# driver.net
KiCad netlist of a schematic drawn in EAGLE
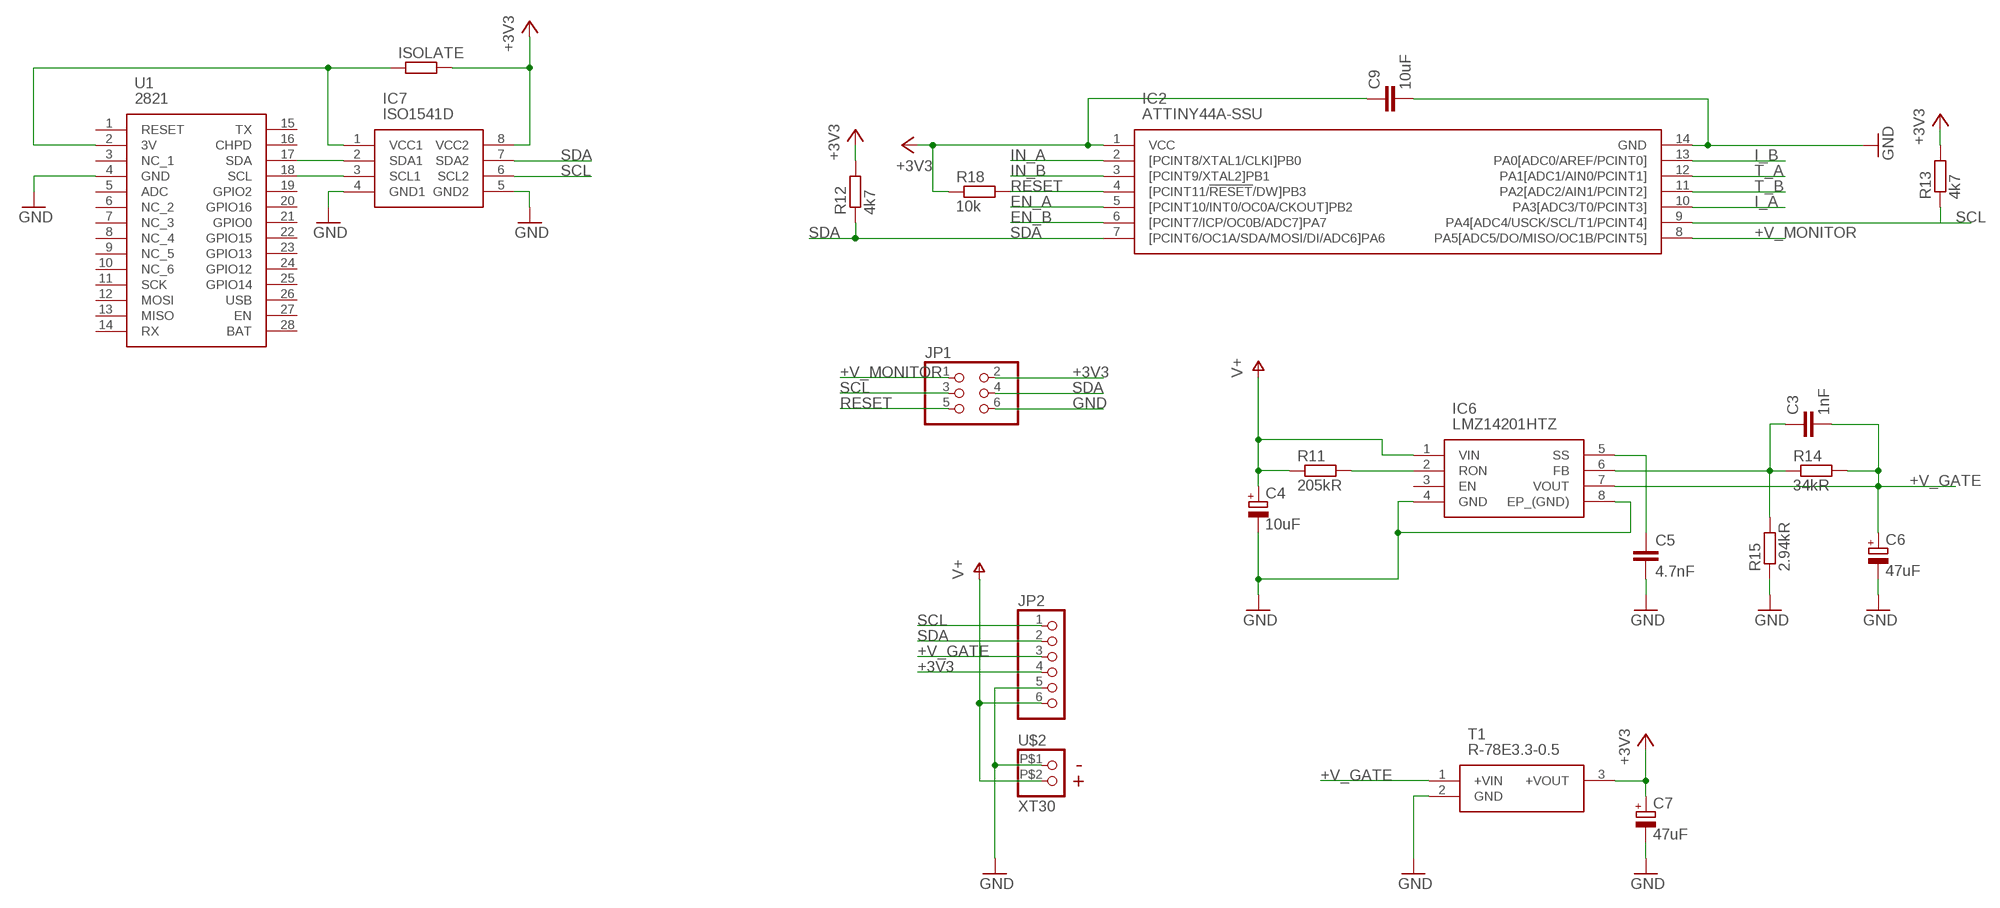
[diagram p0: schematic, sheet 1, part 1 of 2]
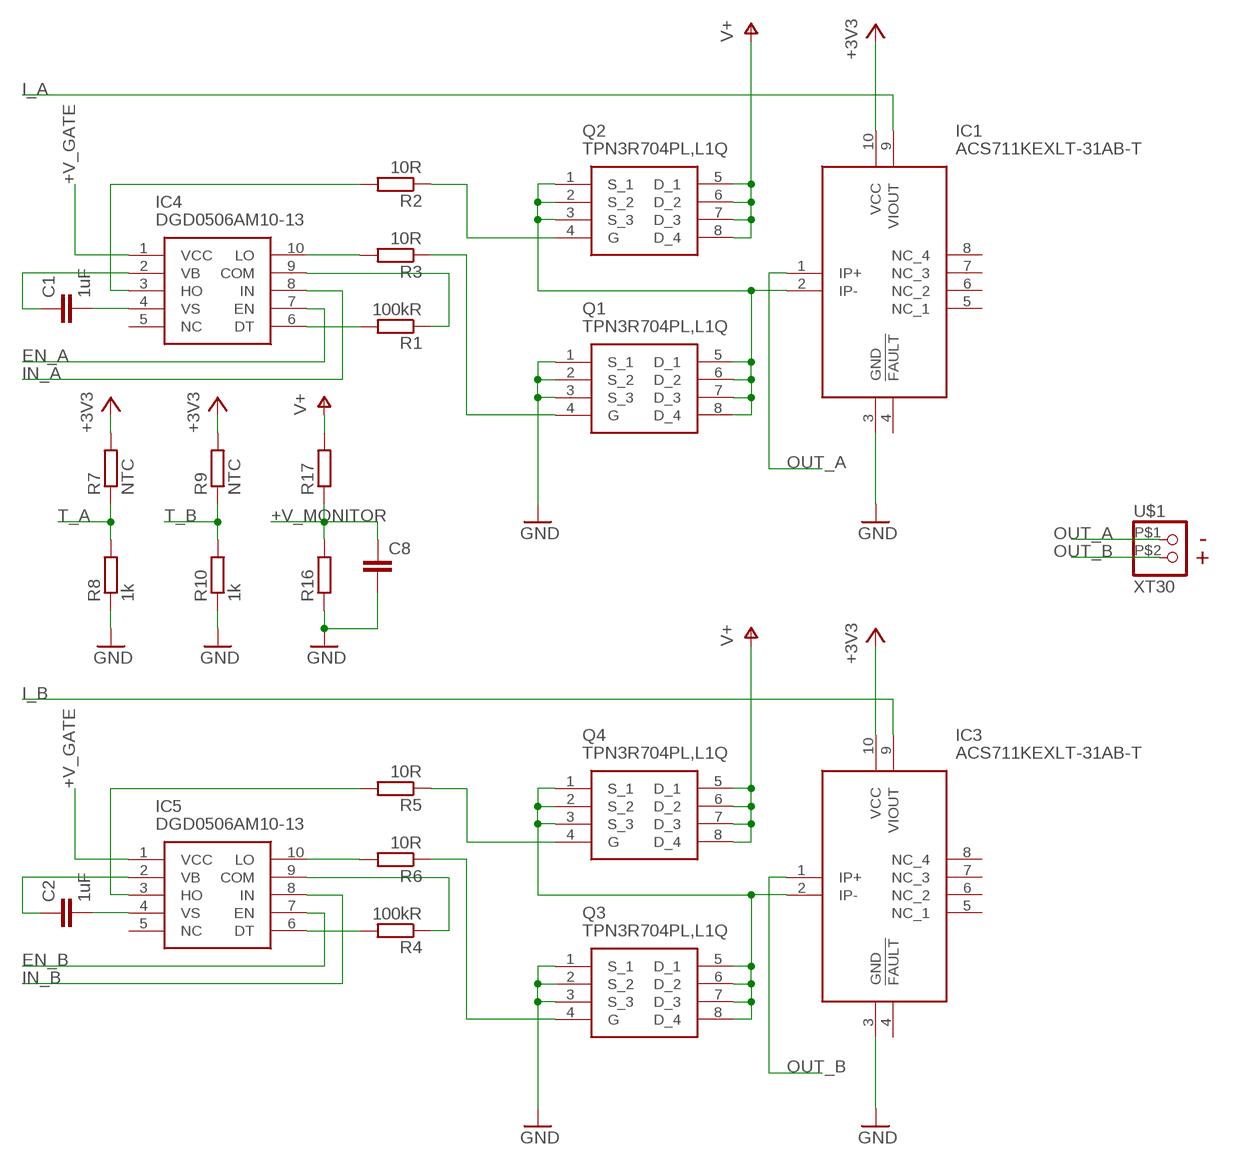
[diagram p1: schematic, sheet 1, part 2 of 2]

(export (version "E")
  (design (tool "Eeschema 10.0.6"))
  (components
    (comp (ref "C1")
      (value "1uF")
      (footprint "eagle-import:C0603")
      (libsource (lib "eagle-import") (part "C-EUC0603"))
    )
    (comp (ref "C2")
      (value "1uF")
      (footprint "eagle-import:C0603")
      (libsource (lib "eagle-import") (part "C-EUC0603"))
    )
    (comp (ref "C3")
      (value "1nF")
      (footprint "eagle-import:C0603")
      (libsource (lib "eagle-import") (part "C-EUC0603"))
    )
    (comp (ref "C4")
      (value "10uF")
      (footprint "eagle-import:E2,5-6E")
      (libsource (lib "eagle-import") (part "CPOL-EUE2,5-6E"))
    )
    (comp (ref "C5")
      (value "4.7nF")
      (footprint "eagle-import:C0603")
      (libsource (lib "eagle-import") (part "C-EUC0603"))
    )
    (comp (ref "C6")
      (value "47uF")
      (footprint "eagle-import:E2,5-6E")
      (libsource (lib "eagle-import") (part "CPOL-EUE2,5-6E"))
    )
    (comp (ref "C7")
      (value "47uF")
      (footprint "eagle-import:E2,5-6E")
      (libsource (lib "eagle-import") (part "CPOL-EUE2,5-6E"))
    )
    (comp (ref "C8")
      (value "C-EUC0603")
      (footprint "eagle-import:C0603")
      (libsource (lib "eagle-import") (part "C-EUC0603"))
    )
    (comp (ref "C9")
      (value "10uF")
      (footprint "eagle-import:C0603")
      (libsource (lib "eagle-import") (part "C-EUC0603"))
    )
    (comp (ref "IC1")
      (value "ACS711KEXLT-31AB-T")
      (footprint "eagle-import:EX-PACKAGE")
      (libsource (lib "eagle-import") (part "ACS711KEXLT-31AB-T"))
    )
    (comp (ref "IC2")
      (value "ATTINY44A-SSU")
      (footprint "eagle-import:SOIC127P600X175-14N")
      (fields
        (field (name "MOUSER_PART_NUMBER") "556-ATTINY44A-SSU")
        (field (name "RS_PART_NUMBER") "1331640P")
      )
      (libsource (lib "eagle-import") (part "ATTINY44A-SSU"))
    )
    (comp (ref "IC3")
      (value "ACS711KEXLT-31AB-T")
      (footprint "eagle-import:EX-PACKAGE")
      (libsource (lib "eagle-import") (part "ACS711KEXLT-31AB-T"))
    )
    (comp (ref "IC4")
      (value "DGD0506AM10-13")
      (footprint "eagle-import:SOP50P490X110-10N")
      (fields
        (field (name "MOUSER_PART_NUMBER") "621-DGD0506AM10-13")
        (field (name "RS_PART_NUMBER") "1827336P")
      )
      (libsource (lib "eagle-import") (part "DGD0506AM10-13"))
    )
    (comp (ref "IC5")
      (value "DGD0506AM10-13")
      (footprint "eagle-import:SOP50P490X110-10N")
      (fields
        (field (name "MOUSER_PART_NUMBER") "621-DGD0506AM10-13")
        (field (name "RS_PART_NUMBER") "1827336P")
      )
      (libsource (lib "eagle-import") (part "DGD0506AM10-13"))
    )
    (comp (ref "IC6")
      (value "LMZ14201HTZ")
      (footprint "eagle-import:NDW0007A")
      (libsource (lib "eagle-import") (part "LMZ14201HTZ"))
    )
    (comp (ref "IC7")
      (value "ISO1541D")
      (footprint "eagle-import:SOIC127P600X175-8N")
      (fields (field (name "MOUSER_PART_NUMBER") "595-ISO1541D") (field (name "RS_PART_NUMBER") "8253075P"))
      (libsource (lib "eagle-import") (part "ISO1541D"))
    )
    (comp (ref "ISOLATE")
      (value "R-EU_R0805")
      (footprint "eagle-import:R0805")
      (libsource (lib "eagle-import") (part "R-EU_R0805"))
    )
    (comp (ref "JP1")
      (value "PINHD-2X3")
      (footprint "eagle-import:2X03")
      (libsource (lib "eagle-import") (part "PINHD-2X3"))
    )
    (comp (ref "JP2")
      (value "PINHD-1X6")
      (footprint "eagle-import:1X06")
      (libsource (lib "eagle-import") (part "PINHD-1X6"))
    )
    (comp (ref "Q1")
      (value "TPN3R704PL,L1Q")
      (footprint "eagle-import:TSON_ADVANCE")
      (fields (field (name "MOUSER_PART_NUMBER") "757-TPN3R704PLL1Q"))
      (libsource (lib "eagle-import") (part "TPN3R704PL,L1Q"))
    )
    (comp (ref "Q2")
      (value "TPN3R704PL,L1Q")
      (footprint "eagle-import:TSON_ADVANCE")
      (fields (field (name "MOUSER_PART_NUMBER") "757-TPN3R704PLL1Q"))
      (libsource (lib "eagle-import") (part "TPN3R704PL,L1Q"))
    )
    (comp (ref "Q3")
      (value "TPN3R704PL,L1Q")
      (footprint "eagle-import:TSON_ADVANCE")
      (fields (field (name "MOUSER_PART_NUMBER") "757-TPN3R704PLL1Q"))
      (libsource (lib "eagle-import") (part "TPN3R704PL,L1Q"))
    )
    (comp (ref "Q4")
      (value "TPN3R704PL,L1Q")
      (footprint "eagle-import:TSON_ADVANCE")
      (fields (field (name "MOUSER_PART_NUMBER") "757-TPN3R704PLL1Q"))
      (libsource (lib "eagle-import") (part "TPN3R704PL,L1Q"))
    )
    (comp (ref "R1")
      (value "100kR")
      (footprint "eagle-import:R0603")
      (libsource (lib "eagle-import") (part "R-EU_R0603"))
    )
    (comp (ref "R2")
      (value "10R")
      (footprint "eagle-import:R0603")
      (libsource (lib "eagle-import") (part "R-EU_R0603"))
    )
    (comp (ref "R3")
      (value "10R")
      (footprint "eagle-import:R0603")
      (libsource (lib "eagle-import") (part "R-EU_R0603"))
    )
    (comp (ref "R4")
      (value "100kR")
      (footprint "eagle-import:R0603")
      (libsource (lib "eagle-import") (part "R-EU_R0603"))
    )
    (comp (ref "R5")
      (value "10R")
      (footprint "eagle-import:R0603")
      (libsource (lib "eagle-import") (part "R-EU_R0603"))
    )
    (comp (ref "R6")
      (value "10R")
      (footprint "eagle-import:R0603")
      (libsource (lib "eagle-import") (part "R-EU_R0603"))
    )
    (comp (ref "R7")
      (value "NTC")
      (footprint "eagle-import:R0603")
      (libsource (lib "eagle-import") (part "R-EU_R0603"))
    )
    (comp (ref "R8")
      (value "1k")
      (footprint "eagle-import:R0603")
      (libsource (lib "eagle-import") (part "R-EU_R0603"))
    )
    (comp (ref "R9")
      (value "NTC")
      (footprint "eagle-import:R0603")
      (libsource (lib "eagle-import") (part "R-EU_R0603"))
    )
    (comp (ref "R10")
      (value "1k")
      (footprint "eagle-import:R0603")
      (libsource (lib "eagle-import") (part "R-EU_R0603"))
    )
    (comp (ref "R11")
      (value "205kR")
      (footprint "eagle-import:R0603")
      (libsource (lib "eagle-import") (part "R-EU_R0603"))
    )
    (comp (ref "R12")
      (value "4k7")
      (footprint "eagle-import:R0603")
      (libsource (lib "eagle-import") (part "R-EU_R0603"))
    )
    (comp (ref "R13")
      (value "4k7")
      (footprint "eagle-import:R0603")
      (libsource (lib "eagle-import") (part "R-EU_R0603"))
    )
    (comp (ref "R14")
      (value "34kR")
      (footprint "eagle-import:R0603")
      (libsource (lib "eagle-import") (part "R-EU_R0603"))
    )
    (comp (ref "R15")
      (value "2.94kR")
      (footprint "eagle-import:R0603")
      (libsource (lib "eagle-import") (part "R-EU_R0603"))
    )
    (comp (ref "R16")
      (value "R-EU_R0603")
      (footprint "eagle-import:R0603")
      (libsource (lib "eagle-import") (part "R-EU_R0603"))
    )
    (comp (ref "R17")
      (value "R-EU_R0603")
      (footprint "eagle-import:R0603")
      (libsource (lib "eagle-import") (part "R-EU_R0603"))
    )
    (comp (ref "R18")
      (value "10k")
      (footprint "eagle-import:R0603")
      (libsource (lib "eagle-import") (part "R-EU_R0603"))
    )
    (comp (ref "T1")
      (value "R-78E3.3-0.5")
      (footprint "eagle-import:SHDRV3W100P0_254_1X3_1160X850X")
      (fields
        (field (name "MOUSER_PART_NUMBER") "919-R-78E3.3-0.5")
        (field (name "RS_PART_NUMBER") "1666497")
      )
      (libsource (lib "eagle-import") (part "R-78E3.3-0.5"))
    )
    (comp (ref "U$1")
      (value "XT30")
      (footprint "eagle-import:XT30")
      (libsource (lib "eagle-import") (part "XT30"))
    )
    (comp (ref "U$2")
      (value "XT30")
      (footprint "eagle-import:XT30")
      (libsource (lib "eagle-import") (part "XT30"))
    )
    (comp (ref "U1")
      (value "2821")
      (footprint "eagle-import:2821")
      (fields (field (name "MOUSER_PART_NUMBER") "485-2821") (field (name "RS_PART_NUMBER") "1245505"))
      (libsource (lib "eagle-import") (part "2821"))
    )
  )
  (nets
    (net (code "1") (name "+3V3") (class "Default")
      (node (ref "C7") (pin "+") (pinfunction "+_+") (pintype "passive"))
      (node (ref "C9") (pin "1") (pinfunction "1_1") (pintype "passive"))
      (node (ref "IC1") (pin "10") (pinfunction "VCC_10") (pintype "bidirectional"))
      (node (ref "IC2") (pin "1") (pinfunction "VCC_1") (pintype "power_in"))
      (node (ref "IC3") (pin "10") (pinfunction "VCC_10") (pintype "bidirectional"))
      (node (ref "IC7") (pin "8") (pinfunction "VCC2_8") (pintype "bidirectional"))
      (node (ref "ISOLATE") (pin "2") (pinfunction "2_2") (pintype "passive"))
      (node (ref "JP1") (pin "2") (pinfunction "2_2") (pintype "passive"))
      (node (ref "JP2") (pin "4") (pinfunction "4_4") (pintype "passive"))
      (node (ref "R12") (pin "2") (pinfunction "2_2") (pintype "passive"))
      (node (ref "R13") (pin "2") (pinfunction "2_2") (pintype "passive"))
      (node (ref "R18") (pin "1") (pinfunction "1_1") (pintype "passive"))
      (node (ref "R7") (pin "2") (pinfunction "2_2") (pintype "passive"))
      (node (ref "R9") (pin "2") (pinfunction "2_2") (pintype "passive"))
      (node (ref "T1") (pin "3") (pinfunction "+VOUT_3") (pintype "output"))
    )
    (net (code "2") (name "/+V_GATE") (class "Default")
      (node (ref "C3") (pin "2") (pinfunction "2_2") (pintype "passive"))
      (node (ref "C6") (pin "+") (pinfunction "+_+") (pintype "passive"))
      (node (ref "IC4") (pin "1") (pinfunction "VCC_1") (pintype "bidirectional"))
      (node (ref "IC5") (pin "1") (pinfunction "VCC_1") (pintype "bidirectional"))
      (node (ref "IC6") (pin "7") (pinfunction "VOUT_7") (pintype "bidirectional"))
      (node (ref "JP2") (pin "3") (pinfunction "3_3") (pintype "passive"))
      (node (ref "R14") (pin "2") (pinfunction "2_2") (pintype "passive"))
      (node (ref "T1") (pin "1") (pinfunction "+VIN_1") (pintype "input"))
    )
    (net (code "3") (name "/+V_MONITOR") (class "Default")
      (node (ref "C8") (pin "1") (pinfunction "1_1") (pintype "passive"))
      (node (ref "IC2") (pin "8") (pinfunction "PA5[ADC5/DO/MISO/OC1B/PCINT5]_8") (pintype "input"))
      (node (ref "JP1") (pin "1") (pinfunction "1_1") (pintype "passive"))
      (node (ref "R16") (pin "2") (pinfunction "2_2") (pintype "passive"))
      (node (ref "R17") (pin "1") (pinfunction "1_1") (pintype "passive"))
    )
    (net (code "4") (name "/EN_A") (class "Default")
      (node (ref "IC2") (pin "5") (pinfunction "[PCINT10/INT0/OC0A/CKOUT]PB2_5") (pintype "output"))
      (node (ref "IC4") (pin "7") (pinfunction "EN_7") (pintype "bidirectional"))
    )
    (net (code "5") (name "/EN_B") (class "Default")
      (node (ref "IC2") (pin "6") (pinfunction "[PCINT7/ICP/OC0B/ADC7]PA7_6") (pintype "input"))
      (node (ref "IC5") (pin "7") (pinfunction "EN_7") (pintype "bidirectional"))
    )
    (net (code "6") (name "/IN_A") (class "Default")
      (node (ref "IC2") (pin "2") (pinfunction "[PCINT8/XTAL1/CLKI]PB0_2") (pintype "input"))
      (node (ref "IC4") (pin "8") (pinfunction "IN_8") (pintype "bidirectional"))
    )
    (net (code "7") (name "/IN_B") (class "Default")
      (node (ref "IC2") (pin "3") (pinfunction "[PCINT9/XTAL2]PB1_3") (pintype "input"))
      (node (ref "IC5") (pin "8") (pinfunction "IN_8") (pintype "bidirectional"))
    )
    (net (code "8") (name "/I_A") (class "Default")
      (node (ref "IC1") (pin "9") (pinfunction "VIOUT_9") (pintype "bidirectional"))
      (node (ref "IC2") (pin "10") (pinfunction "PA3[ADC3/T0/PCINT3]_10") (pintype "input"))
    )
    (net (code "9") (name "/I_B") (class "Default")
      (node (ref "IC2") (pin "13") (pinfunction "PA0[ADC0/AREF/PCINT0]_13") (pintype "input"))
      (node (ref "IC3") (pin "9") (pinfunction "VIOUT_9") (pintype "bidirectional"))
    )
    (net (code "10") (name "/OUT_A") (class "Default")
      (node (ref "IC1") (pin "1") (pinfunction "IP+_1") (pintype "bidirectional"))
      (node (ref "U$1") (pin "P$1") (pinfunction "1_P$1") (pintype "passive"))
    )
    (net (code "11") (name "/OUT_B") (class "Default")
      (node (ref "IC3") (pin "1") (pinfunction "IP+_1") (pintype "bidirectional"))
      (node (ref "U$1") (pin "P$2") (pinfunction "2_P$2") (pintype "passive"))
    )
    (net (code "12") (name "/RESET") (class "Default")
      (node (ref "IC2") (pin "4") (pinfunction "[PCINT11/~{RESET}/DW]PB3_4") (pintype "input"))
      (node (ref "JP1") (pin "5") (pinfunction "5_5") (pintype "passive"))
      (node (ref "R18") (pin "2") (pinfunction "2_2") (pintype "passive"))
    )
    (net (code "13") (name "/SCL") (class "Default")
      (node (ref "IC2") (pin "9") (pinfunction "PA4[ADC4/USCK/SCL/T1/PCINT4]_9") (pintype "input"))
      (node (ref "IC7") (pin "6") (pinfunction "SCL2_6") (pintype "bidirectional"))
      (node (ref "JP1") (pin "3") (pinfunction "3_3") (pintype "passive"))
      (node (ref "JP2") (pin "1") (pinfunction "1_1") (pintype "passive"))
      (node (ref "R13") (pin "1") (pinfunction "1_1") (pintype "passive"))
    )
    (net (code "14") (name "/SDA") (class "Default")
      (node (ref "IC2") (pin "7") (pinfunction "[PCINT6/OC1A/SDA/MOSI/DI/ADC6]PA6_7") (pintype "input"))
      (node (ref "IC7") (pin "7") (pinfunction "SDA2_7") (pintype "bidirectional"))
      (node (ref "JP1") (pin "4") (pinfunction "4_4") (pintype "passive"))
      (node (ref "JP2") (pin "2") (pinfunction "2_2") (pintype "passive"))
      (node (ref "R12") (pin "1") (pinfunction "1_1") (pintype "passive"))
    )
    (net (code "15") (name "/T_A") (class "Default")
      (node (ref "IC2") (pin "12") (pinfunction "PA1[ADC1/AIN0/PCINT1]_12") (pintype "input"))
      (node (ref "R7") (pin "1") (pinfunction "1_1") (pintype "passive"))
      (node (ref "R8") (pin "2") (pinfunction "2_2") (pintype "passive"))
    )
    (net (code "16") (name "/T_B") (class "Default")
      (node (ref "IC2") (pin "11") (pinfunction "PA2[ADC2/AIN1/PCINT2]_11") (pintype "input"))
      (node (ref "R10") (pin "2") (pinfunction "2_2") (pintype "passive"))
      (node (ref "R9") (pin "1") (pinfunction "1_1") (pintype "passive"))
    )
    (net (code "17") (name "GND") (class "Default")
      (node (ref "C4") (pin "-") (pinfunction "-_-") (pintype "passive"))
      (node (ref "C5") (pin "2") (pinfunction "2_2") (pintype "passive"))
      (node (ref "C6") (pin "-") (pinfunction "-_-") (pintype "passive"))
      (node (ref "C7") (pin "-") (pinfunction "-_-") (pintype "passive"))
      (node (ref "C8") (pin "2") (pinfunction "2_2") (pintype "passive"))
      (node (ref "C9") (pin "2") (pinfunction "2_2") (pintype "passive"))
      (node (ref "IC1") (pin "3") (pinfunction "GND_3") (pintype "bidirectional"))
      (node (ref "IC2") (pin "14") (pinfunction "GND_14") (pintype "power_in"))
      (node (ref "IC3") (pin "3") (pinfunction "GND_3") (pintype "bidirectional"))
      (node (ref "IC6") (pin "4") (pinfunction "GND_4") (pintype "bidirectional"))
      (node (ref "IC6") (pin "8") (pinfunction "EP_(GND)_8") (pintype "bidirectional"))
      (node (ref "IC7") (pin "4") (pinfunction "GND1_4") (pintype "bidirectional"))
      (node (ref "IC7") (pin "5") (pinfunction "GND2_5") (pintype "bidirectional"))
      (node (ref "JP1") (pin "6") (pinfunction "6_6") (pintype "passive"))
      (node (ref "JP2") (pin "5") (pinfunction "5_5") (pintype "passive"))
      (node (ref "Q1") (pin "1") (pinfunction "S_1_1") (pintype "bidirectional"))
      (node (ref "Q1") (pin "2") (pinfunction "S_2_2") (pintype "bidirectional"))
      (node (ref "Q1") (pin "3") (pinfunction "S_3_3") (pintype "bidirectional"))
      (node (ref "Q3") (pin "1") (pinfunction "S_1_1") (pintype "bidirectional"))
      (node (ref "Q3") (pin "2") (pinfunction "S_2_2") (pintype "bidirectional"))
      (node (ref "Q3") (pin "3") (pinfunction "S_3_3") (pintype "bidirectional"))
      (node (ref "R10") (pin "1") (pinfunction "1_1") (pintype "passive"))
      (node (ref "R15") (pin "1") (pinfunction "1_1") (pintype "passive"))
      (node (ref "R16") (pin "1") (pinfunction "1_1") (pintype "passive"))
      (node (ref "R8") (pin "1") (pinfunction "1_1") (pintype "passive"))
      (node (ref "T1") (pin "2") (pinfunction "GND_2") (pintype "power_in"))
      (node (ref "U$2") (pin "P$1") (pinfunction "1_P$1") (pintype "passive"))
      (node (ref "U1") (pin "4") (pinfunction "GND_4") (pintype "bidirectional"))
    )
    (net (code "18") (name "Net-(IC1-IP-)") (class "Default")
      (node (ref "IC1") (pin "2") (pinfunction "IP-_2") (pintype "bidirectional"))
      (node (ref "Q1") (pin "5") (pinfunction "D_1_5") (pintype "bidirectional"))
      (node (ref "Q1") (pin "6") (pinfunction "D_2_6") (pintype "bidirectional"))
      (node (ref "Q1") (pin "7") (pinfunction "D_3_7") (pintype "bidirectional"))
      (node (ref "Q1") (pin "8") (pinfunction "D_4_8") (pintype "bidirectional"))
      (node (ref "Q2") (pin "1") (pinfunction "S_1_1") (pintype "bidirectional"))
      (node (ref "Q2") (pin "2") (pinfunction "S_2_2") (pintype "bidirectional"))
      (node (ref "Q2") (pin "3") (pinfunction "S_3_3") (pintype "bidirectional"))
    )
    (net (code "19") (name "Net-(IC3-IP-)") (class "Default")
      (node (ref "IC3") (pin "2") (pinfunction "IP-_2") (pintype "bidirectional"))
      (node (ref "Q3") (pin "5") (pinfunction "D_1_5") (pintype "bidirectional"))
      (node (ref "Q3") (pin "6") (pinfunction "D_2_6") (pintype "bidirectional"))
      (node (ref "Q3") (pin "7") (pinfunction "D_3_7") (pintype "bidirectional"))
      (node (ref "Q3") (pin "8") (pinfunction "D_4_8") (pintype "bidirectional"))
      (node (ref "Q4") (pin "1") (pinfunction "S_1_1") (pintype "bidirectional"))
      (node (ref "Q4") (pin "2") (pinfunction "S_2_2") (pintype "bidirectional"))
      (node (ref "Q4") (pin "3") (pinfunction "S_3_3") (pintype "bidirectional"))
    )
    (net (code "20") (name "Net-(IC4-COM)") (class "Default")
      (node (ref "IC4") (pin "9") (pinfunction "COM_9") (pintype "bidirectional"))
      (node (ref "R1") (pin "1") (pinfunction "1_1") (pintype "passive"))
    )
    (net (code "21") (name "Net-(IC4-DT)") (class "Default")
      (node (ref "IC4") (pin "6") (pinfunction "DT_6") (pintype "bidirectional"))
      (node (ref "R1") (pin "2") (pinfunction "2_2") (pintype "passive"))
    )
    (net (code "22") (name "Net-(IC4-HO)") (class "Default")
      (node (ref "IC4") (pin "3") (pinfunction "HO_3") (pintype "bidirectional"))
      (node (ref "R2") (pin "2") (pinfunction "2_2") (pintype "passive"))
    )
    (net (code "23") (name "Net-(IC4-LO)") (class "Default")
      (node (ref "IC4") (pin "10") (pinfunction "LO_10") (pintype "bidirectional"))
      (node (ref "R3") (pin "2") (pinfunction "2_2") (pintype "passive"))
    )
    (net (code "24") (name "Net-(IC4-VB)") (class "Default")
      (node (ref "C1") (pin "1") (pinfunction "1_1") (pintype "passive"))
      (node (ref "IC4") (pin "2") (pinfunction "VB_2") (pintype "bidirectional"))
    )
    (net (code "25") (name "Net-(IC4-VS)") (class "Default")
      (node (ref "C1") (pin "2") (pinfunction "2_2") (pintype "passive"))
      (node (ref "IC4") (pin "4") (pinfunction "VS_4") (pintype "bidirectional"))
    )
    (net (code "26") (name "Net-(IC5-COM)") (class "Default")
      (node (ref "IC5") (pin "9") (pinfunction "COM_9") (pintype "bidirectional"))
      (node (ref "R4") (pin "1") (pinfunction "1_1") (pintype "passive"))
    )
    (net (code "27") (name "Net-(IC5-DT)") (class "Default")
      (node (ref "IC5") (pin "6") (pinfunction "DT_6") (pintype "bidirectional"))
      (node (ref "R4") (pin "2") (pinfunction "2_2") (pintype "passive"))
    )
    (net (code "28") (name "Net-(IC5-HO)") (class "Default")
      (node (ref "IC5") (pin "3") (pinfunction "HO_3") (pintype "bidirectional"))
      (node (ref "R5") (pin "2") (pinfunction "2_2") (pintype "passive"))
    )
    (net (code "29") (name "Net-(IC5-LO)") (class "Default")
      (node (ref "IC5") (pin "10") (pinfunction "LO_10") (pintype "bidirectional"))
      (node (ref "R6") (pin "2") (pinfunction "2_2") (pintype "passive"))
    )
    (net (code "30") (name "Net-(IC5-VB)") (class "Default")
      (node (ref "C2") (pin "1") (pinfunction "1_1") (pintype "passive"))
      (node (ref "IC5") (pin "2") (pinfunction "VB_2") (pintype "bidirectional"))
    )
    (net (code "31") (name "Net-(IC5-VS)") (class "Default")
      (node (ref "C2") (pin "2") (pinfunction "2_2") (pintype "passive"))
      (node (ref "IC5") (pin "4") (pinfunction "VS_4") (pintype "bidirectional"))
    )
    (net (code "32") (name "Net-(IC6-FB)") (class "Default")
      (node (ref "C3") (pin "1") (pinfunction "1_1") (pintype "passive"))
      (node (ref "IC6") (pin "6") (pinfunction "FB_6") (pintype "bidirectional"))
      (node (ref "R14") (pin "1") (pinfunction "1_1") (pintype "passive"))
      (node (ref "R15") (pin "2") (pinfunction "2_2") (pintype "passive"))
    )
    (net (code "33") (name "Net-(IC6-RON)") (class "Default")
      (node (ref "IC6") (pin "2") (pinfunction "RON_2") (pintype "bidirectional"))
      (node (ref "R11") (pin "2") (pinfunction "2_2") (pintype "passive"))
    )
    (net (code "34") (name "Net-(IC6-SS)") (class "Default")
      (node (ref "C5") (pin "1") (pinfunction "1_1") (pintype "passive"))
      (node (ref "IC6") (pin "5") (pinfunction "SS_5") (pintype "bidirectional"))
    )
    (net (code "35") (name "Net-(IC7-SCL1)") (class "Default")
      (node (ref "IC7") (pin "3") (pinfunction "SCL1_3") (pintype "bidirectional"))
      (node (ref "U1") (pin "18") (pinfunction "SCL_18") (pintype "bidirectional"))
    )
    (net (code "36") (name "Net-(IC7-SDA1)") (class "Default")
      (node (ref "IC7") (pin "2") (pinfunction "SDA1_2") (pintype "bidirectional"))
      (node (ref "U1") (pin "17") (pinfunction "SDA_17") (pintype "bidirectional"))
    )
    (net (code "37") (name "Net-(IC7-VCC1)") (class "Default")
      (node (ref "IC7") (pin "1") (pinfunction "VCC1_1") (pintype "power_in"))
      (node (ref "ISOLATE") (pin "1") (pinfunction "1_1") (pintype "passive"))
      (node (ref "U1") (pin "2") (pinfunction "3V_2") (pintype "bidirectional"))
    )
    (net (code "38") (name "Net-(Q1-G)") (class "Default")
      (node (ref "Q1") (pin "4") (pinfunction "G_4") (pintype "bidirectional"))
      (node (ref "R3") (pin "1") (pinfunction "1_1") (pintype "passive"))
    )
    (net (code "39") (name "Net-(Q2-G)") (class "Default")
      (node (ref "Q2") (pin "4") (pinfunction "G_4") (pintype "bidirectional"))
      (node (ref "R2") (pin "1") (pinfunction "1_1") (pintype "passive"))
    )
    (net (code "40") (name "Net-(Q3-G)") (class "Default")
      (node (ref "Q3") (pin "4") (pinfunction "G_4") (pintype "bidirectional"))
      (node (ref "R6") (pin "1") (pinfunction "1_1") (pintype "passive"))
    )
    (net (code "41") (name "Net-(Q4-G)") (class "Default")
      (node (ref "Q4") (pin "4") (pinfunction "G_4") (pintype "bidirectional"))
      (node (ref "R5") (pin "1") (pinfunction "1_1") (pintype "passive"))
    )
    (net (code "42") (name "V+") (class "Default")
      (node (ref "C4") (pin "+") (pinfunction "+_+") (pintype "passive"))
      (node (ref "IC6") (pin "1") (pinfunction "VIN_1") (pintype "bidirectional"))
      (node (ref "JP2") (pin "6") (pinfunction "6_6") (pintype "passive"))
      (node (ref "Q2") (pin "5") (pinfunction "D_1_5") (pintype "bidirectional"))
      (node (ref "Q2") (pin "6") (pinfunction "D_2_6") (pintype "bidirectional"))
      (node (ref "Q2") (pin "7") (pinfunction "D_3_7") (pintype "bidirectional"))
      (node (ref "Q2") (pin "8") (pinfunction "D_4_8") (pintype "bidirectional"))
      (node (ref "Q4") (pin "5") (pinfunction "D_1_5") (pintype "bidirectional"))
      (node (ref "Q4") (pin "6") (pinfunction "D_2_6") (pintype "bidirectional"))
      (node (ref "Q4") (pin "7") (pinfunction "D_3_7") (pintype "bidirectional"))
      (node (ref "Q4") (pin "8") (pinfunction "D_4_8") (pintype "bidirectional"))
      (node (ref "R11") (pin "1") (pinfunction "1_1") (pintype "passive"))
      (node (ref "R17") (pin "2") (pinfunction "2_2") (pintype "passive"))
      (node (ref "U$2") (pin "P$2") (pinfunction "2_P$2") (pintype "passive"))
    )
    (net (code "43") (name "unconnected-(IC1-NC_1-Pad5)") (class "Default")
      (node (ref "IC1") (pin "5") (pinfunction "NC_1_5") (pintype "bidirectional"))
    )
    (net (code "44") (name "unconnected-(IC1-NC_2-Pad6)") (class "Default")
      (node (ref "IC1") (pin "6") (pinfunction "NC_2_6") (pintype "bidirectional"))
    )
    (net (code "45") (name "unconnected-(IC1-NC_3-Pad7)") (class "Default")
      (node (ref "IC1") (pin "7") (pinfunction "NC_3_7") (pintype "bidirectional"))
    )
    (net (code "46") (name "unconnected-(IC1-NC_4-Pad8)") (class "Default")
      (node (ref "IC1") (pin "8") (pinfunction "NC_4_8") (pintype "bidirectional"))
    )
    (net (code "47") (name "unconnected-(IC1-~{FAULT}-Pad4)") (class "Default")
      (node (ref "IC1") (pin "4") (pinfunction "~{FAULT}_4") (pintype "bidirectional"))
    )
    (net (code "48") (name "unconnected-(IC3-NC_1-Pad5)") (class "Default")
      (node (ref "IC3") (pin "5") (pinfunction "NC_1_5") (pintype "bidirectional"))
    )
    (net (code "49") (name "unconnected-(IC3-NC_2-Pad6)") (class "Default")
      (node (ref "IC3") (pin "6") (pinfunction "NC_2_6") (pintype "bidirectional"))
    )
    (net (code "50") (name "unconnected-(IC3-NC_3-Pad7)") (class "Default")
      (node (ref "IC3") (pin "7") (pinfunction "NC_3_7") (pintype "bidirectional"))
    )
    (net (code "51") (name "unconnected-(IC3-NC_4-Pad8)") (class "Default")
      (node (ref "IC3") (pin "8") (pinfunction "NC_4_8") (pintype "bidirectional"))
    )
    (net (code "52") (name "unconnected-(IC3-~{FAULT}-Pad4)") (class "Default")
      (node (ref "IC3") (pin "4") (pinfunction "~{FAULT}_4") (pintype "bidirectional"))
    )
    (net (code "53") (name "unconnected-(IC4-NC-Pad5)") (class "Default")
      (node (ref "IC4") (pin "5") (pinfunction "NC_5") (pintype "no_connect"))
    )
    (net (code "54") (name "unconnected-(IC5-NC-Pad5)") (class "Default")
      (node (ref "IC5") (pin "5") (pinfunction "NC_5") (pintype "no_connect"))
    )
    (net (code "55") (name "unconnected-(IC6-EN-Pad3)") (class "Default")
      (node (ref "IC6") (pin "3") (pinfunction "EN_3") (pintype "bidirectional"))
    )
    (net (code "56") (name "unconnected-(U1-ADC-Pad5)") (class "Default")
      (node (ref "U1") (pin "5") (pinfunction "ADC_5") (pintype "bidirectional"))
    )
    (net (code "57") (name "unconnected-(U1-BAT-Pad28)") (class "Default")
      (node (ref "U1") (pin "28") (pinfunction "BAT_28") (pintype "bidirectional"))
    )
    (net (code "58") (name "unconnected-(U1-CHPD-Pad16)") (class "Default")
      (node (ref "U1") (pin "16") (pinfunction "CHPD_16") (pintype "bidirectional"))
    )
    (net (code "59") (name "unconnected-(U1-EN-Pad27)") (class "Default")
      (node (ref "U1") (pin "27") (pinfunction "EN_27") (pintype "bidirectional"))
    )
    (net (code "60") (name "unconnected-(U1-GPIO0-Pad21)") (class "Default")
      (node (ref "U1") (pin "21") (pinfunction "GPIO0_21") (pintype "bidirectional"))
    )
    (net (code "61") (name "unconnected-(U1-GPIO2-Pad19)") (class "Default")
      (node (ref "U1") (pin "19") (pinfunction "GPIO2_19") (pintype "bidirectional"))
    )
    (net (code "62") (name "unconnected-(U1-GPIO12-Pad24)") (class "Default")
      (node (ref "U1") (pin "24") (pinfunction "GPIO12_24") (pintype "bidirectional"))
    )
    (net (code "63") (name "unconnected-(U1-GPIO13-Pad23)") (class "Default")
      (node (ref "U1") (pin "23") (pinfunction "GPIO13_23") (pintype "bidirectional"))
    )
    (net (code "64") (name "unconnected-(U1-GPIO14-Pad25)") (class "Default")
      (node (ref "U1") (pin "25") (pinfunction "GPIO14_25") (pintype "bidirectional"))
    )
    (net (code "65") (name "unconnected-(U1-GPIO15-Pad22)") (class "Default")
      (node (ref "U1") (pin "22") (pinfunction "GPIO15_22") (pintype "bidirectional"))
    )
    (net (code "66") (name "unconnected-(U1-GPIO16-Pad20)") (class "Default")
      (node (ref "U1") (pin "20") (pinfunction "GPIO16_20") (pintype "bidirectional"))
    )
    (net (code "67") (name "unconnected-(U1-MISO-Pad13)") (class "Default")
      (node (ref "U1") (pin "13") (pinfunction "MISO_13") (pintype "bidirectional"))
    )
    (net (code "68") (name "unconnected-(U1-MOSI-Pad12)") (class "Default")
      (node (ref "U1") (pin "12") (pinfunction "MOSI_12") (pintype "bidirectional"))
    )
    (net (code "69") (name "unconnected-(U1-NC_1-Pad3)") (class "Default")
      (node (ref "U1") (pin "3") (pinfunction "NC_1_3") (pintype "bidirectional"))
    )
    (net (code "70") (name "unconnected-(U1-NC_2-Pad6)") (class "Default")
      (node (ref "U1") (pin "6") (pinfunction "NC_2_6") (pintype "bidirectional"))
    )
    (net (code "71") (name "unconnected-(U1-NC_3-Pad7)") (class "Default")
      (node (ref "U1") (pin "7") (pinfunction "NC_3_7") (pintype "bidirectional"))
    )
    (net (code "72") (name "unconnected-(U1-NC_4-Pad8)") (class "Default")
      (node (ref "U1") (pin "8") (pinfunction "NC_4_8") (pintype "bidirectional"))
    )
    (net (code "73") (name "unconnected-(U1-NC_5-Pad9)") (class "Default")
      (node (ref "U1") (pin "9") (pinfunction "NC_5_9") (pintype "bidirectional"))
    )
    (net (code "74") (name "unconnected-(U1-NC_6-Pad10)") (class "Default")
      (node (ref "U1") (pin "10") (pinfunction "NC_6_10") (pintype "bidirectional"))
    )
    (net (code "75") (name "unconnected-(U1-RESET-Pad1)") (class "Default")
      (node (ref "U1") (pin "1") (pinfunction "RESET_1") (pintype "bidirectional"))
    )
    (net (code "76") (name "unconnected-(U1-RX-Pad14)") (class "Default")
      (node (ref "U1") (pin "14") (pinfunction "RX_14") (pintype "bidirectional"))
    )
    (net (code "77") (name "unconnected-(U1-SCK-Pad11)") (class "Default")
      (node (ref "U1") (pin "11") (pinfunction "SCK_11") (pintype "bidirectional"))
    )
    (net (code "78") (name "unconnected-(U1-TX-Pad15)") (class "Default")
      (node (ref "U1") (pin "15") (pinfunction "TX_15") (pintype "bidirectional"))
    )
    (net (code "79") (name "unconnected-(U1-USB-Pad26)") (class "Default")
      (node (ref "U1") (pin "26") (pinfunction "USB_26") (pintype "bidirectional"))
    )
  )
)
